# Top.net
KiCad netlist of a schematic drawn in Altium Designer
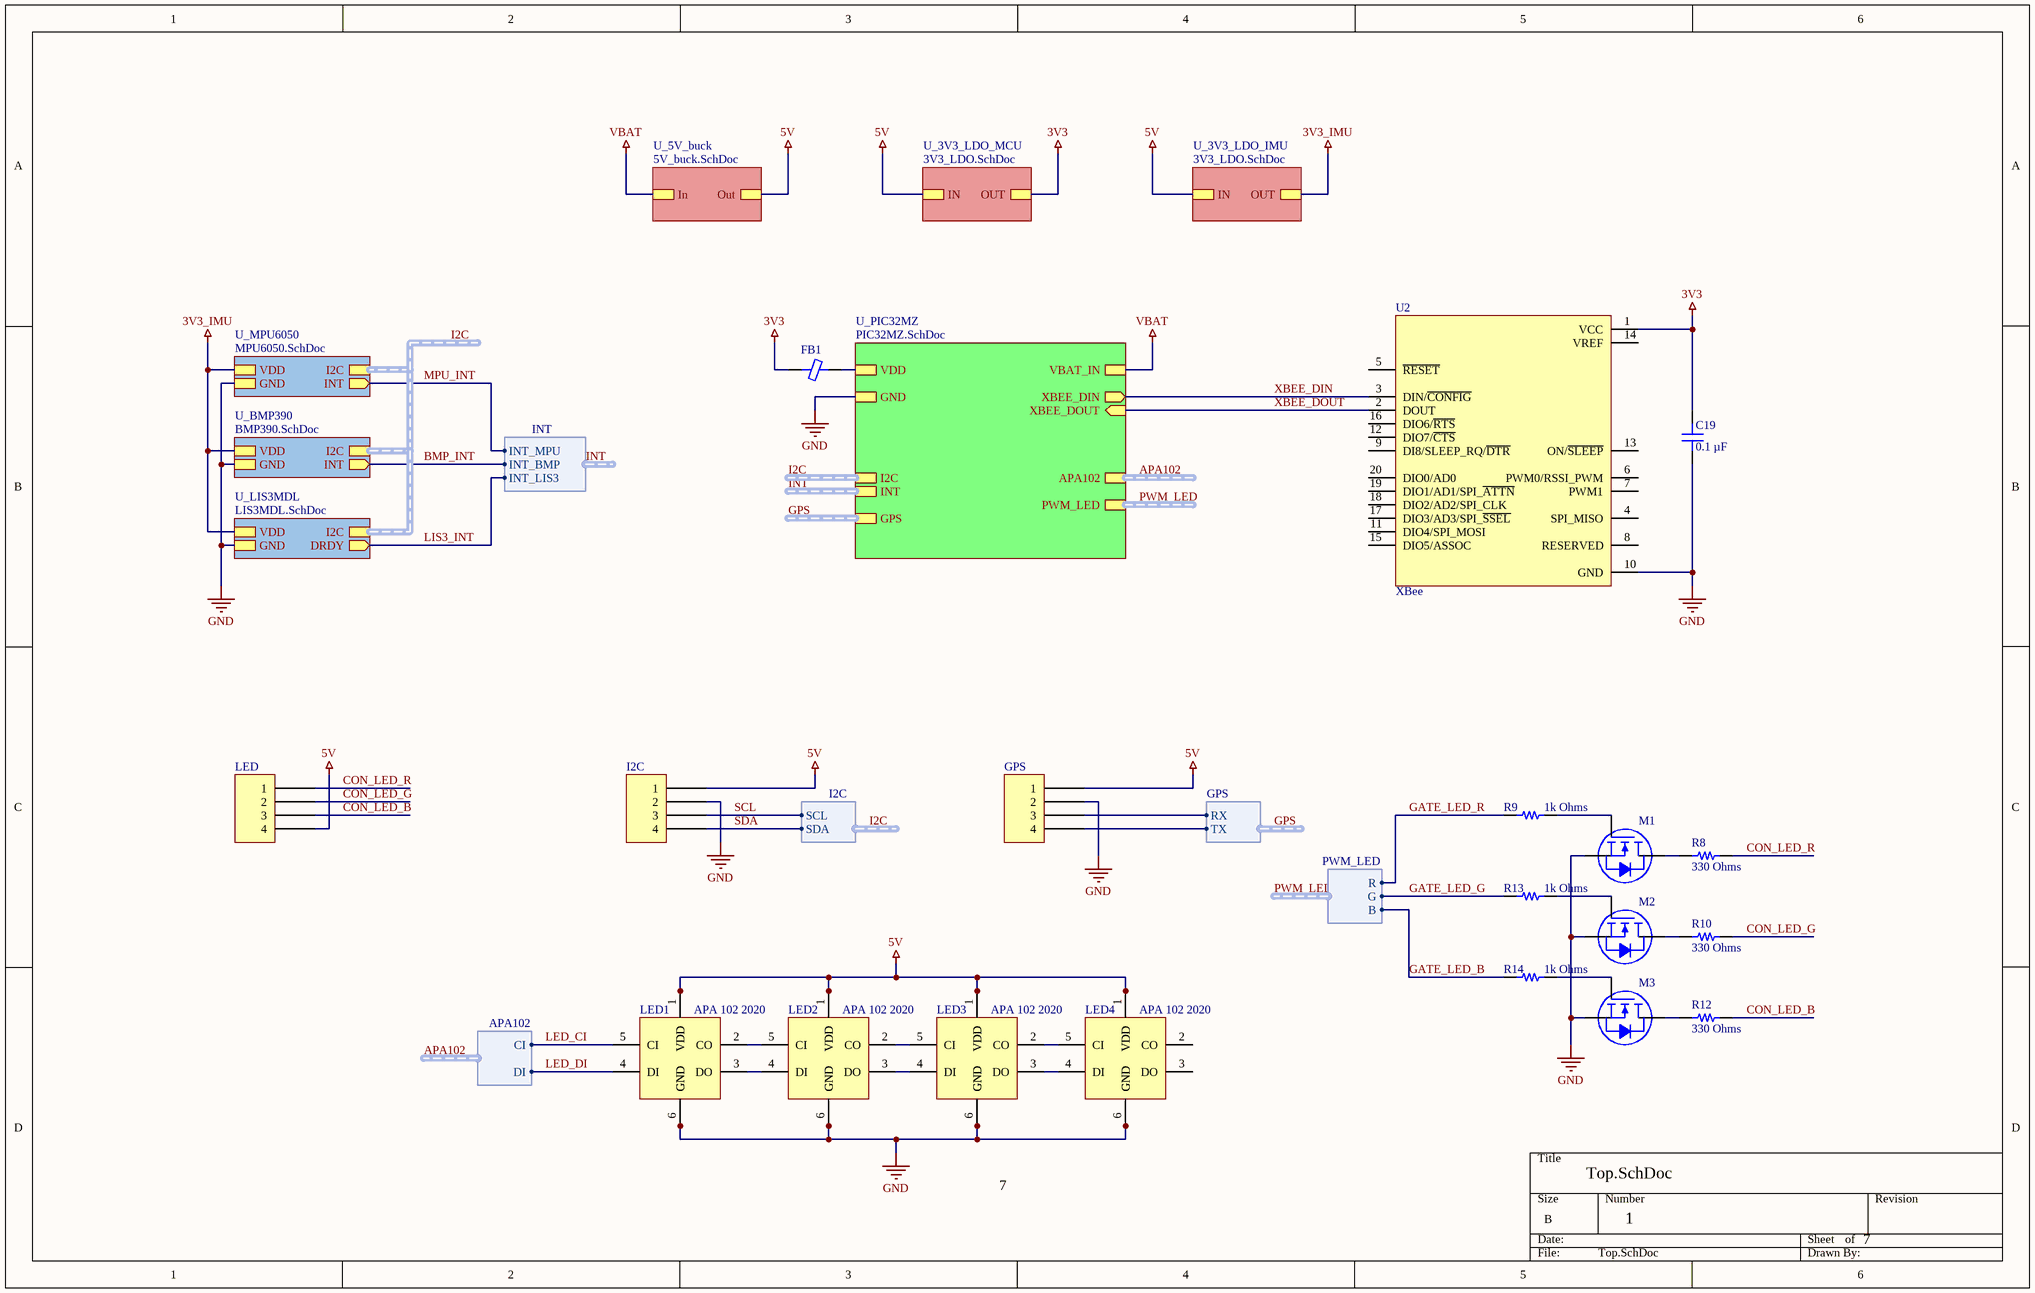
[diagram p0: Top.SchDoc]

(export (version "E")
  (design (tool "Eeschema 10.0.6"))
  (components
    (comp (ref "C19")
      (value "0.1 µF")
      (footprint "CAP 0402_1005")
      (description "CAP CER 0.1UF 16V X7R 0402")
      (fields (field (name "PART NUMBER") "C0402C104K4RACAUTO") (field (name "MANUFACTURER") "KEMET"))
      (libsource (lib "Celestial Altium Library - altium_library") (part "Capacitor"))
    )
    (comp (ref "FB1")
      (value "~")
      (footprint "FER 0805_2012")
      (description "FERRITE BEAD 0805 1LN")
      (fields
        (field (name "PART NUMBER") "2508051017Y0")
        (field (name "MANUFACTURER") "Fair-Rite Products Corp.")
      )
      (libsource (lib "Celestial Altium Library - altium_library") (part "Ferrite Chip"))
    )
    (comp (ref "GPS")
      (value "SM04B-SRSS-TB(LF)(SN)")
      (footprint "JST SM04B-SRSS-TB")
      (description "CONN HEADER SMD R/A 4POS 1MM")
      (fields (field (name "MANUFACTURER") "JST Sales America Inc."))
      (libsource (lib "Celestial Altium Library - altium_library") (part "4 Pin"))
    )
    (comp (ref "I2C")
      (value "SM04B-SRSS-TB(LF)(SN)")
      (footprint "JST SM04B-SRSS-TB")
      (description "CONN HEADER SMD R/A 4POS 1MM")
      (fields (field (name "MANUFACTURER") "JST Sales America Inc."))
      (libsource (lib "Celestial Altium Library - altium_library") (part "4 Pin"))
    )
    (comp (ref "LED")
      (value "SM04B-SRSS-TB(LF)(SN)")
      (footprint "JST SM04B-SRSS-TB")
      (description "CONN HEADER SMD R/A 4POS 1MM")
      (fields (field (name "MANUFACTURER") "JST Sales America Inc."))
      (libsource (lib "Celestial Altium Library - altium_library") (part "4 Pin"))
    )
    (comp (ref "LED1")
      (value "APA 102 2020")
      (footprint "LED_APA-102-2020-256-8")
      (description "8-pin type LED three-color RGB Dimming control")
      (fields (field (name "MP") "APA-102-2020-256-8") (field (name "MF") "iPixel LED Light Co."))
      (libsource (lib "IC") (part "APA-102-2020-256-8"))
    )
    (comp (ref "LED2")
      (value "APA 102 2020")
      (footprint "LED_APA-102-2020-256-8")
      (description "8-pin type LED three-color RGB Dimming control")
      (fields (field (name "MP") "APA-102-2020-256-8") (field (name "MF") "iPixel LED Light Co."))
      (libsource (lib "IC") (part "APA-102-2020-256-8"))
    )
    (comp (ref "LED3")
      (value "APA 102 2020")
      (footprint "LED_APA-102-2020-256-8")
      (description "8-pin type LED three-color RGB Dimming control")
      (fields (field (name "MP") "APA-102-2020-256-8") (field (name "MF") "iPixel LED Light Co."))
      (libsource (lib "IC") (part "APA-102-2020-256-8"))
    )
    (comp (ref "LED4")
      (value "APA 102 2020")
      (footprint "LED_APA-102-2020-256-8")
      (description "8-pin type LED three-color RGB Dimming control")
      (fields (field (name "MP") "APA-102-2020-256-8") (field (name "MF") "iPixel LED Light Co."))
      (libsource (lib "IC") (part "APA-102-2020-256-8"))
    )
    (comp (ref "M1")
      (value "BSS123-7-F")
      (footprint "DIODES SOT-23-3")
      (description "MOSFET N-CH 100V 170MA SOT23-3")
      (fields (field (name "MANUFACTURER") "Diodes Incorporated"))
      (libsource (lib "Celestial Altium Library - altium_library") (part "DIODES INC MOSFET N-CH SOT-23-3"))
    )
    (comp (ref "M2")
      (value "BSS123-7-F")
      (footprint "DIODES SOT-23-3")
      (description "MOSFET N-CH 100V 170MA SOT23-3")
      (fields (field (name "MANUFACTURER") "Diodes Incorporated"))
      (libsource (lib "Celestial Altium Library - altium_library") (part "DIODES INC MOSFET N-CH SOT-23-3"))
    )
    (comp (ref "M3")
      (value "BSS123-7-F")
      (footprint "DIODES SOT-23-3")
      (description "MOSFET N-CH 100V 170MA SOT23-3")
      (fields (field (name "MANUFACTURER") "Diodes Incorporated"))
      (libsource (lib "Celestial Altium Library - altium_library") (part "DIODES INC MOSFET N-CH SOT-23-3"))
    )
    (comp (ref "R8")
      (value "330 Ohms")
      (footprint "RES 0603_1608")
      (description "RES 10K OHM 0.1% 1/16W 0603")
      (fields
        (field (name "PART NUMBER") "RNCS0603BKE10K0")
        (field (name "MANUFACTURER") "Stackpole Electronics Inc")
      )
      (libsource (lib "Celestial Altium Library - altium_library") (part "Resistor"))
    )
    (comp (ref "R9")
      (value "1k Ohms")
      (footprint "RES 0402_1005")
      (description "RES 330 OHM 5% 1/16W 0402")
      (fields (field (name "PART NUMBER") "CRCW0402330RJNEDC") (field (name "MANUFACTURER") "Vishay Dale"))
      (libsource (lib "Celestial Altium Library - altium_library") (part "Resistor"))
    )
    (comp (ref "R10")
      (value "330 Ohms")
      (footprint "RES 0603_1608")
      (description "RES 10K OHM 0.1% 1/16W 0603")
      (fields
        (field (name "PART NUMBER") "RNCS0603BKE10K0")
        (field (name "MANUFACTURER") "Stackpole Electronics Inc")
      )
      (libsource (lib "Celestial Altium Library - altium_library") (part "Resistor"))
    )
    (comp (ref "R12")
      (value "330 Ohms")
      (footprint "RES 0603_1608")
      (description "RES 10K OHM 0.1% 1/16W 0603")
      (fields
        (field (name "PART NUMBER") "RNCS0603BKE10K0")
        (field (name "MANUFACTURER") "Stackpole Electronics Inc")
      )
      (libsource (lib "Celestial Altium Library - altium_library") (part "Resistor"))
    )
    (comp (ref "R13")
      (value "1k Ohms")
      (footprint "RES 0402_1005")
      (description "RES 330 OHM 5% 1/16W 0402")
      (fields (field (name "PART NUMBER") "CRCW0402330RJNEDC") (field (name "MANUFACTURER") "Vishay Dale"))
      (libsource (lib "Celestial Altium Library - altium_library") (part "Resistor"))
    )
    (comp (ref "R14")
      (value "1k Ohms")
      (footprint "RES 0402_1005")
      (description "RES 330 OHM 5% 1/16W 0402")
      (fields (field (name "PART NUMBER") "CRCW0402330RJNEDC") (field (name "MANUFACTURER") "Vishay Dale"))
      (libsource (lib "Celestial Altium Library - altium_library") (part "Resistor"))
    )
    (comp (ref "U2")
      (value "XBee")
      (footprint "XBee -SMD Header")
      (description "802.15.4 Transceiver Module 2.4GHz Antenna Not Included, U.FL Through Hole")
      (libsource (lib "IC") (part "XBee SMD Header"))
    )
  )
  (nets
    (net (code "13") (name "/CON_LED_B") (class "Default")
      (node (ref "LED") (pin "3") (pinfunction "3_3") (pintype "passive"))
      (node (ref "R12") (pin "2") (pinfunction "2_2") (pintype "passive"))
    )
    (net (code "14") (name "/CON_LED_G") (class "Default")
      (node (ref "LED") (pin "2") (pinfunction "2_2") (pintype "passive"))
      (node (ref "R10") (pin "2") (pinfunction "2_2") (pintype "passive"))
    )
    (net (code "15") (name "/CON_LED_R") (class "Default")
      (node (ref "LED") (pin "1") (pinfunction "1_1") (pintype "passive"))
      (node (ref "R8") (pin "2") (pinfunction "2_2") (pintype "passive"))
    )
    (net (code "16") (name "/GATE_LED_B") (class "Default")
      (node (ref "R14") (pin "2") (pinfunction "2_2") (pintype "passive"))
    )
    (net (code "17") (name "/GATE_LED_G") (class "Default")
      (node (ref "R13") (pin "2") (pinfunction "2_2") (pintype "passive"))
    )
    (net (code "18") (name "/GATE_LED_R") (class "Default")
      (node (ref "R9") (pin "2") (pinfunction "2_2") (pintype "passive"))
    )
    (net (code "22") (name "/LED_CI") (class "Default")
      (node (ref "LED1") (pin "5") (pinfunction "CI_5") (pintype "passive"))
    )
    (net (code "23") (name "/LED_DI") (class "Default")
      (node (ref "LED1") (pin "4") (pinfunction "DI_4") (pintype "passive"))
    )
    (net (code "27") (name "/RX") (class "Default")
      (node (ref "GPS") (pin "3") (pinfunction "3_3") (pintype "passive"))
    )
    (net (code "28") (name "/SCL") (class "Default")
      (node (ref "I2C") (pin "3") (pinfunction "3_3") (pintype "passive"))
    )
    (net (code "29") (name "/SDA") (class "Default")
      (node (ref "I2C") (pin "4") (pinfunction "4_4") (pintype "passive"))
    )
    (net (code "30") (name "/TX") (class "Default")
      (node (ref "GPS") (pin "4") (pinfunction "4_4") (pintype "passive"))
    )
    (net (code "31") (name "/VDD") (class "Default")
      (node (ref "FB1") (pin "2") (pinfunction "2_2") (pintype "passive"))
    )
    (net (code "32") (name "/XBEE_DIN") (class "Default")
      (node (ref "U2") (pin "3") (pinfunction "DIN/~{CONFIG}_3") (pintype "passive"))
    )
    (net (code "33") (name "/XBEE_DOUT") (class "Default")
      (node (ref "U2") (pin "2") (pinfunction "DOUT_2") (pintype "passive"))
    )
    (net (code "39") (name "3V3") (class "Default")
      (node (ref "C19") (pin "2") (pinfunction "2_2") (pintype "passive"))
      (node (ref "FB1") (pin "1") (pinfunction "1_1") (pintype "passive"))
      (node (ref "U2") (pin "1") (pinfunction "VCC_1") (pintype "power_in"))
    )
    (net (code "41") (name "5V") (class "Default")
      (node (ref "GPS") (pin "1") (pinfunction "1_1") (pintype "passive"))
      (node (ref "I2C") (pin "1") (pinfunction "1_1") (pintype "passive"))
      (node (ref "LED") (pin "4") (pinfunction "4_4") (pintype "passive"))
      (node (ref "LED1") (pin "1") (pinfunction "VDD_1") (pintype "power_in"))
      (node (ref "LED1") (pin "8") (pinfunction "VDD_8") (pintype "power_in"))
      (node (ref "LED2") (pin "1") (pinfunction "VDD_1") (pintype "power_in"))
      (node (ref "LED2") (pin "8") (pinfunction "VDD_8") (pintype "power_in"))
      (node (ref "LED3") (pin "1") (pinfunction "VDD_1") (pintype "power_in"))
      (node (ref "LED3") (pin "8") (pinfunction "VDD_8") (pintype "power_in"))
      (node (ref "LED4") (pin "1") (pinfunction "VDD_1") (pintype "power_in"))
      (node (ref "LED4") (pin "8") (pinfunction "VDD_8") (pintype "power_in"))
    )
    (net (code "42") (name "GND") (class "Default")
      (node (ref "C19") (pin "1") (pinfunction "1_1") (pintype "passive"))
      (node (ref "GPS") (pin "2") (pinfunction "2_2") (pintype "passive"))
      (node (ref "I2C") (pin "2") (pinfunction "2_2") (pintype "passive"))
      (node (ref "LED1") (pin "6") (pinfunction "GND_6") (pintype "power_in"))
      (node (ref "LED1") (pin "7") (pinfunction "GND_7") (pintype "power_in"))
      (node (ref "LED2") (pin "6") (pinfunction "GND_6") (pintype "power_in"))
      (node (ref "LED2") (pin "7") (pinfunction "GND_7") (pintype "power_in"))
      (node (ref "LED3") (pin "6") (pinfunction "GND_6") (pintype "power_in"))
      (node (ref "LED3") (pin "7") (pinfunction "GND_7") (pintype "power_in"))
      (node (ref "LED4") (pin "6") (pinfunction "GND_6") (pintype "power_in"))
      (node (ref "LED4") (pin "7") (pinfunction "GND_7") (pintype "power_in"))
      (node (ref "M1") (pin "2") (pinfunction "S_2") (pintype "passive"))
      (node (ref "M2") (pin "2") (pinfunction "S_2") (pintype "passive"))
      (node (ref "M3") (pin "2") (pinfunction "S_2") (pintype "passive"))
      (node (ref "U2") (pin "10") (pinfunction "GND_10") (pintype "power_in"))
    )
    (net (code "43") (name "Net-(LED1-CO)") (class "Default")
      (node (ref "LED1") (pin "2") (pinfunction "CO_2") (pintype "passive"))
      (node (ref "LED2") (pin "5") (pinfunction "CI_5") (pintype "passive"))
    )
    (net (code "44") (name "Net-(LED1-DO)") (class "Default")
      (node (ref "LED1") (pin "3") (pinfunction "DO_3") (pintype "passive"))
      (node (ref "LED2") (pin "4") (pinfunction "DI_4") (pintype "passive"))
    )
    (net (code "45") (name "Net-(LED2-CO)") (class "Default")
      (node (ref "LED2") (pin "2") (pinfunction "CO_2") (pintype "passive"))
      (node (ref "LED3") (pin "5") (pinfunction "CI_5") (pintype "passive"))
    )
    (net (code "46") (name "Net-(LED2-DO)") (class "Default")
      (node (ref "LED2") (pin "3") (pinfunction "DO_3") (pintype "passive"))
      (node (ref "LED3") (pin "4") (pinfunction "DI_4") (pintype "passive"))
    )
    (net (code "47") (name "Net-(LED3-CO)") (class "Default")
      (node (ref "LED3") (pin "2") (pinfunction "CO_2") (pintype "passive"))
      (node (ref "LED4") (pin "5") (pinfunction "CI_5") (pintype "passive"))
    )
    (net (code "48") (name "Net-(LED3-DO)") (class "Default")
      (node (ref "LED3") (pin "3") (pinfunction "DO_3") (pintype "passive"))
      (node (ref "LED4") (pin "4") (pinfunction "DI_4") (pintype "passive"))
    )
    (net (code "49") (name "Net-(M1-D)") (class "Default")
      (node (ref "M1") (pin "3") (pinfunction "D_3") (pintype "passive"))
      (node (ref "R8") (pin "1") (pinfunction "1_1") (pintype "passive"))
    )
    (net (code "50") (name "Net-(M1-G)") (class "Default")
      (node (ref "M1") (pin "1") (pinfunction "G_1") (pintype "passive"))
      (node (ref "R9") (pin "1") (pinfunction "1_1") (pintype "passive"))
    )
    (net (code "51") (name "Net-(M2-D)") (class "Default")
      (node (ref "M2") (pin "3") (pinfunction "D_3") (pintype "passive"))
      (node (ref "R10") (pin "1") (pinfunction "1_1") (pintype "passive"))
    )
    (net (code "52") (name "Net-(M2-G)") (class "Default")
      (node (ref "M2") (pin "1") (pinfunction "G_1") (pintype "passive"))
      (node (ref "R13") (pin "1") (pinfunction "1_1") (pintype "passive"))
    )
    (net (code "53") (name "Net-(M3-D)") (class "Default")
      (node (ref "M3") (pin "3") (pinfunction "D_3") (pintype "passive"))
      (node (ref "R12") (pin "1") (pinfunction "1_1") (pintype "passive"))
    )
    (net (code "54") (name "Net-(M3-G)") (class "Default")
      (node (ref "M3") (pin "1") (pinfunction "G_1") (pintype "passive"))
      (node (ref "R14") (pin "1") (pinfunction "1_1") (pintype "passive"))
    )
    (net (code "56") (name "unconnected-(LED4-CO-Pad2)") (class "Default")
      (node (ref "LED4") (pin "2") (pinfunction "CO_2") (pintype "passive"))
    )
    (net (code "57") (name "unconnected-(LED4-DO-Pad3)") (class "Default")
      (node (ref "LED4") (pin "3") (pinfunction "DO_3") (pintype "passive"))
    )
    (net (code "58") (name "unconnected-(U2-DI8{slash}SLEEP_RQ{slash}~{DTR}-Pad9)") (class "Default")
      (node (ref "U2") (pin "9") (pinfunction "DI8/SLEEP_RQ/~{DTR}_9") (pintype "passive"))
    )
    (net (code "59") (name "unconnected-(U2-DIO0{slash}AD0-Pad20)") (class "Default")
      (node (ref "U2") (pin "20") (pinfunction "DIO0/AD0_20") (pintype "passive"))
    )
    (net (code "60") (name "unconnected-(U2-DIO1{slash}AD1{slash}SPI_~{ATTN}-Pad19)") (class "Default")
      (node (ref "U2") (pin "19") (pinfunction "DIO1/AD1/SPI_~{ATTN}_19") (pintype "passive"))
    )
    (net (code "61") (name "unconnected-(U2-DIO2{slash}AD2{slash}SPI_CLK-Pad18)") (class "Default")
      (node (ref "U2") (pin "18") (pinfunction "DIO2/AD2/SPI_CLK_18") (pintype "passive"))
    )
    (net (code "62") (name "unconnected-(U2-DIO3{slash}AD3{slash}SPI_~{SSEL}-Pad17)") (class "Default")
      (node (ref "U2") (pin "17") (pinfunction "DIO3/AD3/SPI_~{SSEL}_17") (pintype "passive"))
    )
    (net (code "63") (name "unconnected-(U2-DIO4{slash}SPI_MOSI-Pad11)") (class "Default")
      (node (ref "U2") (pin "11") (pinfunction "DIO4/SPI_MOSI_11") (pintype "passive"))
    )
    (net (code "64") (name "unconnected-(U2-DIO5{slash}ASSOC-Pad15)") (class "Default")
      (node (ref "U2") (pin "15") (pinfunction "DIO5/ASSOC_15") (pintype "passive"))
    )
    (net (code "65") (name "unconnected-(U2-DIO6{slash}~{RTS}-Pad16)") (class "Default")
      (node (ref "U2") (pin "16") (pinfunction "DIO6/~{RTS}_16") (pintype "passive"))
    )
    (net (code "66") (name "unconnected-(U2-DIO7{slash}~{CTS}-Pad12)") (class "Default")
      (node (ref "U2") (pin "12") (pinfunction "DIO7/~{CTS}_12") (pintype "passive"))
    )
    (net (code "67") (name "unconnected-(U2-ON{slash}~{SLEEP}-Pad13)") (class "Default")
      (node (ref "U2") (pin "13") (pinfunction "ON/~{SLEEP}_13") (pintype "passive"))
    )
    (net (code "68") (name "unconnected-(U2-PWM0{slash}RSSI_PWM-Pad6)") (class "Default")
      (node (ref "U2") (pin "6") (pinfunction "PWM0/RSSI_PWM_6") (pintype "passive"))
    )
    (net (code "69") (name "unconnected-(U2-PWM1-Pad7)") (class "Default")
      (node (ref "U2") (pin "7") (pinfunction "PWM1_7") (pintype "passive"))
    )
    (net (code "70") (name "unconnected-(U2-RESERVED-Pad8)") (class "Default")
      (node (ref "U2") (pin "8") (pinfunction "RESERVED_8") (pintype "passive"))
    )
    (net (code "71") (name "unconnected-(U2-SPI_MISO-Pad4)") (class "Default")
      (node (ref "U2") (pin "4") (pinfunction "SPI_MISO_4") (pintype "passive"))
    )
    (net (code "72") (name "unconnected-(U2-VREF-Pad14)") (class "Default")
      (node (ref "U2") (pin "14") (pinfunction "VREF_14") (pintype "power_in"))
    )
    (net (code "73") (name "unconnected-(U2-~{RESET}-Pad5)") (class "Default")
      (node (ref "U2") (pin "5") (pinfunction "~{RESET}_5") (pintype "passive"))
    )
  )
)
